# POWER.net
KiCad netlist of a schematic drawn in Altium Designer
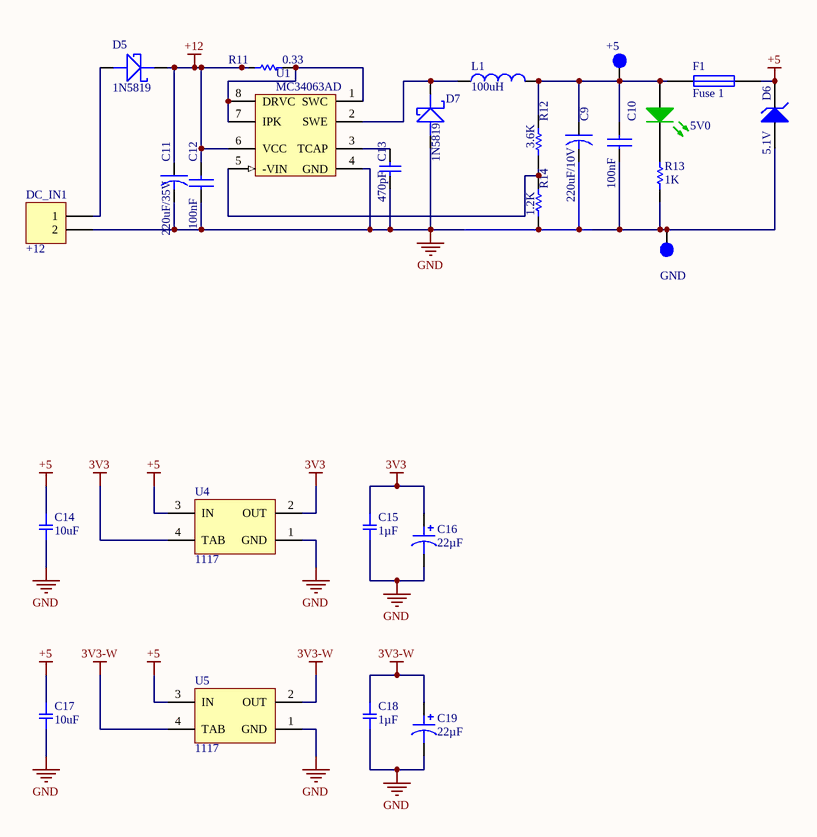
[diagram p0: POWER.SchDoc]

(export (version "E")
  (design (tool "Eeschema 10.0.6"))
  (components
    (comp (ref "+5")
      (value "Test Point")
      (footprint "PIN1")
      (description "No PCB Compunent need")
      (libsource (lib "GeneralLibrary") (part "Test Point"))
    )
    (comp (ref "5V0")
      (value "LED-GREEN")
      (footprint "DIOSMD1206")
      (description "General Propuse Ga/As LED")
      (libsource (lib "GeneralLibrary") (part "LED-GREEN"))
    )
    (comp (ref "C9")
      (value "220uF/10V")
      (footprint "Radial-B8")
      (description "Electrolytic Capacitor")
      (libsource (lib "GSMRTI_SCH") (part "CAPACITOR"))
    )
    (comp (ref "C10")
      (value "100nF")
      (footprint "0805")
      (description "63V Multilayer")
      (libsource (lib "GSMRTI_SCH") (part "C"))
    )
    (comp (ref "C11")
      (value "220uF/35V")
      (footprint "Radial-C10")
      (description "Electrolytic Capacitor")
      (libsource (lib "GSMRTI_SCH") (part "CAPACITOR"))
    )
    (comp (ref "C12")
      (value "100nF")
      (footprint "0805")
      (description "63V Multilayer")
      (libsource (lib "GSMRTI_SCH") (part "C"))
    )
    (comp (ref "C13")
      (value "470pF")
      (footprint "0805")
      (description "Capacitor")
      (fields (field (name "PUBLISHER") "Altium Limited"))
      (libsource (lib "Miscellaneous Devices") (part "Cap"))
    )
    (comp (ref "C14")
      (value "10uF")
      (footprint "0805")
      (description "CAP CER 1.0UF 16V X7R 0805")
      (fields
        (field (name "DIGI-KEY PART NUMBER") "490-12590-1-ND")
        (field (name "PART NUMBER") "GCM219R71C105KA37J")
      )
      (libsource (lib "Cap_805") (part "GCM219R71C105KA37J"))
    )
    (comp (ref "C15")
      (value "1µF")
      (footprint "0805")
      (description "CAP CER 1UF 10V X7R 0805")
      (fields
        (field (name "DIGI-KEY PART NUMBER") "490-11595-1-ND")
        (field (name "PART NUMBER") "GRM21BR71A105KA01K")
      )
      (libsource (lib "Cap_805") (part "GRM21BR71A105KA01K"))
    )
    (comp (ref "C16")
      (value "22µF")
      (footprint "3216[1206]")
      (description "CAP TANT 22UF 10% 10V 1206")
      (fields (field (name "PART NUMBER") "F931A226KAA") (field (name "MANUFACTURER") "AVX Corporation"))
      (libsource (lib "Celestial Altium Library - altium_library") (part "Polarised Capacitor"))
    )
    (comp (ref "C17")
      (value "10uF")
      (footprint "0805")
      (description "CAP CER 1.0UF 16V X7R 0805")
      (fields
        (field (name "DIGI-KEY PART NUMBER") "490-12590-1-ND")
        (field (name "PART NUMBER") "GCM219R71C105KA37J")
      )
      (libsource (lib "Cap_805") (part "GCM219R71C105KA37J"))
    )
    (comp (ref "C18")
      (value "1µF")
      (footprint "0805")
      (description "CAP CER 1UF 10V X7R 0805")
      (fields
        (field (name "DIGI-KEY PART NUMBER") "490-11595-1-ND")
        (field (name "PART NUMBER") "GRM21BR71A105KA01K")
      )
      (libsource (lib "Cap_805") (part "GRM21BR71A105KA01K"))
    )
    (comp (ref "C19")
      (value "22µF")
      (footprint "3216[1206]")
      (description "CAP TANT 22UF 10% 10V 1206")
      (fields (field (name "PART NUMBER") "F931A226KAA") (field (name "MANUFACTURER") "AVX Corporation"))
      (libsource (lib "Celestial Altium Library - altium_library") (part "Polarised Capacitor"))
    )
    (comp (ref "D5")
      (value "1N5819")
      (footprint "DIODE-SMA")
      (description "Schottky Diode")
      (libsource (lib "TaghiLib14_5_87") (part "DIODE SCHOTTKY"))
    )
    (comp (ref "D6")
      (value "5.1V")
      (footprint "DIODE-SMA")
      (description "Zener Diode")
      (fields (field (name "PUBLISHER") "Altium Limited"))
      (libsource (lib "Miscellaneous Devices") (part "D Zener"))
    )
    (comp (ref "D7")
      (value "1N5819")
      (footprint "DIODE-SMA")
      (description "Schottky Diode")
      (libsource (lib "TaghiLib14_5_87") (part "DIODE SCHOTTKY"))
    )
    (comp (ref "DC_IN1")
      (value "+12")
      (footprint "Phoenix_2")
      (description "Header, 2-Pin")
      (fields (field (name "PUBLISHER") "Altium Limited"))
      (libsource (lib "Miscellaneous Connectors") (part "Header 2"))
    )
    (comp (ref "F1")
      (value "Fuse 1")
      (footprint "3216[1206]")
      (description "Fuse")
      (fields (field (name "PUBLISHER") "Altium Limited"))
      (libsource (lib "Miscellaneous Devices") (part "Fuse 1"))
    )
    (comp (ref "GND")
      (value "Test Point")
      (footprint "PIN1")
      (description "No PCB Compunent need")
      (libsource (lib "GeneralLibrary") (part "Test Point"))
    )
    (comp (ref "L1") (value "100uH") (footprint "L_Right") (libsource (lib "*") (part "INDUCTOR")))
    (comp (ref "R11")
      (value "0.33")
      (footprint "1206")
      (description "Resistor")
      (fields (field (name "PUBLISHER") "Altium Limited"))
      (libsource (lib "Miscellaneous Devices") (part "Res1"))
    )
    (comp (ref "R12")
      (value "3.6K")
      (footprint "0805")
      (description "Resistor")
      (fields (field (name "PUBLISHER") "Altium Limited"))
      (libsource (lib "Miscellaneous Devices") (part "Res1"))
    )
    (comp (ref "R13")
      (value "1K")
      (footprint "0805")
      (description "Resistor")
      (libsource (lib "GeneralLibrary") (part "1-ResistorW"))
    )
    (comp (ref "R14")
      (value "1.2K")
      (footprint "0805")
      (description "Resistor")
      (fields (field (name "PUBLISHER") "Altium Limited"))
      (libsource (lib "Miscellaneous Devices") (part "Res1"))
    )
    (comp (ref "U1")
      (value "MC34063AD")
      (footprint "soic-8")
      (description "DC-to-DC Converter Control Circuit")
      (fields (field (name "PUBLISHER") "Altium Limited"))
      (libsource (lib "Motorola Power Mgt DC-DC Converter") (part "MC34063AD"))
    )
    (comp (ref "U4")
      (value "1117")
      (footprint "SOT223")
      (description "x.x Volt, 800mA Low-Dropout Linear Regulator, 4-pin SOT-223")
      (fields (field (name "DESIGNER") "Ali Hafizi"))
      (libsource (lib "Altium") (part "AMS1117-x.x"))
    )
    (comp (ref "U5")
      (value "1117")
      (footprint "SOT223")
      (description "x.x Volt, 800mA Low-Dropout Linear Regulator, 4-pin SOT-223")
      (fields (field (name "DESIGNER") "Ali Hafizi"))
      (libsource (lib "Altium") (part "AMS1117-x.x"))
    )
  )
  (nets
    (net (code "1") (name "+5") (class "Default")
      (node (ref "C14") (pin "1") (pinfunction "1_1") (pintype "passive"))
      (node (ref "C17") (pin "1") (pinfunction "1_1") (pintype "passive"))
      (node (ref "D6") (pin "2") (pinfunction "K_2") (pintype "passive"))
      (node (ref "F1") (pin "2") (pinfunction "2_2") (pintype "passive"))
      (node (ref "U4") (pin "3") (pinfunction "IN_3") (pintype "power_in"))
      (node (ref "U5") (pin "3") (pinfunction "IN_3") (pintype "power_in"))
    )
    (net (code "2") (name "+12") (class "Default")
      (node (ref "C11") (pin "1") (pinfunction "1_1") (pintype "passive"))
      (node (ref "C12") (pin "2") (pinfunction "2_2") (pintype "passive"))
      (node (ref "D5") (pin "2") (pinfunction "K_2") (pintype "passive"))
      (node (ref "R11") (pin "2") (pinfunction "2_2") (pintype "passive"))
      (node (ref "U1") (pin "6") (pinfunction "VCC_6") (pintype "power_in"))
    )
    (net (code "3") (name "3V3") (class "Default")
      (node (ref "C15") (pin "1") (pinfunction "1_1") (pintype "passive"))
      (node (ref "C16") (pin "1") (pinfunction "1_1") (pintype "passive"))
      (node (ref "U4") (pin "2") (pinfunction "OUT_2") (pintype "power_in"))
      (node (ref "U4") (pin "4") (pinfunction "TAB_4") (pintype "power_in"))
    )
    (net (code "4") (name "3V3-W") (class "Default")
      (node (ref "C18") (pin "1") (pinfunction "1_1") (pintype "passive"))
      (node (ref "C19") (pin "1") (pinfunction "1_1") (pintype "passive"))
      (node (ref "U5") (pin "2") (pinfunction "OUT_2") (pintype "power_in"))
      (node (ref "U5") (pin "4") (pinfunction "TAB_4") (pintype "power_in"))
    )
    (net (code "5") (name "GND") (class "Default")
      (node (ref "C10") (pin "1") (pinfunction "1_1") (pintype "passive"))
      (node (ref "C11") (pin "2") (pinfunction "2_2") (pintype "passive"))
      (node (ref "C12") (pin "1") (pinfunction "1_1") (pintype "passive"))
      (node (ref "C13") (pin "2") (pinfunction "2_2") (pintype "passive"))
      (node (ref "C14") (pin "2") (pinfunction "2_2") (pintype "passive"))
      (node (ref "C15") (pin "2") (pinfunction "2_2") (pintype "passive"))
      (node (ref "C16") (pin "2") (pinfunction "2_2") (pintype "passive"))
      (node (ref "C17") (pin "2") (pinfunction "2_2") (pintype "passive"))
      (node (ref "C18") (pin "2") (pinfunction "2_2") (pintype "passive"))
      (node (ref "C19") (pin "2") (pinfunction "2_2") (pintype "passive"))
      (node (ref "C9") (pin "2") (pinfunction "2_2") (pintype "passive"))
      (node (ref "D6") (pin "1") (pinfunction "A_1") (pintype "passive"))
      (node (ref "D7") (pin "1") (pinfunction "A_1") (pintype "passive"))
      (node (ref "DC_IN1") (pin "2") (pinfunction "2_2") (pintype "passive"))
      (node (ref "GND") (pin "1") (pinfunction "1_1") (pintype "passive"))
      (node (ref "R13") (pin "2") (pinfunction "2_2") (pintype "passive"))
      (node (ref "R14") (pin "1") (pinfunction "1_1") (pintype "passive"))
      (node (ref "U1") (pin "4") (pinfunction "GND_4") (pintype "power_in"))
      (node (ref "U4") (pin "1") (pinfunction "GND_1") (pintype "power_in"))
      (node (ref "U5") (pin "1") (pinfunction "GND_1") (pintype "power_in"))
    )
    (net (code "6") (name "Net-(5V0-A)") (class "Default")
      (node (ref "+5") (pin "1") (pinfunction "1_1") (pintype "passive"))
      (node (ref "5V0") (pin "1") (pinfunction "A_1") (pintype "passive"))
      (node (ref "C10") (pin "2") (pinfunction "2_2") (pintype "passive"))
      (node (ref "C9") (pin "1") (pinfunction "1_1") (pintype "passive"))
      (node (ref "F1") (pin "1") (pinfunction "1_1") (pintype "passive"))
      (node (ref "L1") (pin "2") (pinfunction "2_2") (pintype "passive"))
      (node (ref "R12") (pin "2") (pinfunction "2_2") (pintype "passive"))
    )
    (net (code "7") (name "Net-(5V0-K)") (class "Default")
      (node (ref "5V0") (pin "2") (pinfunction "K_2") (pintype "passive"))
      (node (ref "R13") (pin "1") (pinfunction "1_1") (pintype "passive"))
    )
    (net (code "8") (name "Net-(D5-A)") (class "Default")
      (node (ref "D5") (pin "1") (pinfunction "A_1") (pintype "passive"))
      (node (ref "DC_IN1") (pin "1") (pinfunction "1_1") (pintype "passive"))
    )
    (net (code "9") (name "Net-(D7-K)") (class "Default")
      (node (ref "D7") (pin "2") (pinfunction "K_2") (pintype "passive"))
      (node (ref "L1") (pin "1") (pinfunction "1_1") (pintype "passive"))
      (node (ref "U1") (pin "2") (pinfunction "SWE_2") (pintype "open_emitter"))
    )
    (net (code "10") (name "Net-(U1--VIN)") (class "Default")
      (node (ref "R12") (pin "1") (pinfunction "1_1") (pintype "passive"))
      (node (ref "R14") (pin "2") (pinfunction "2_2") (pintype "passive"))
      (node (ref "U1") (pin "5") (pinfunction "-VIN_5") (pintype "input"))
    )
    (net (code "11") (name "Net-(U1-DRVC)") (class "Default")
      (node (ref "R11") (pin "1") (pinfunction "1_1") (pintype "passive"))
      (node (ref "U1") (pin "1") (pinfunction "SWC_1") (pintype "open_collector"))
      (node (ref "U1") (pin "7") (pinfunction "IPK_7") (pintype "passive"))
      (node (ref "U1") (pin "8") (pinfunction "DRVC_8") (pintype "open_collector"))
    )
    (net (code "12") (name "Net-(U1-TCAP)") (class "Default")
      (node (ref "C13") (pin "1") (pinfunction "1_1") (pintype "passive"))
      (node (ref "U1") (pin "3") (pinfunction "TCAP_3") (pintype "passive"))
    )
  )
)
